# FOTA_MCU_ICSP_Communication.net
KiCad netlist of a schematic drawn in Altium Designer
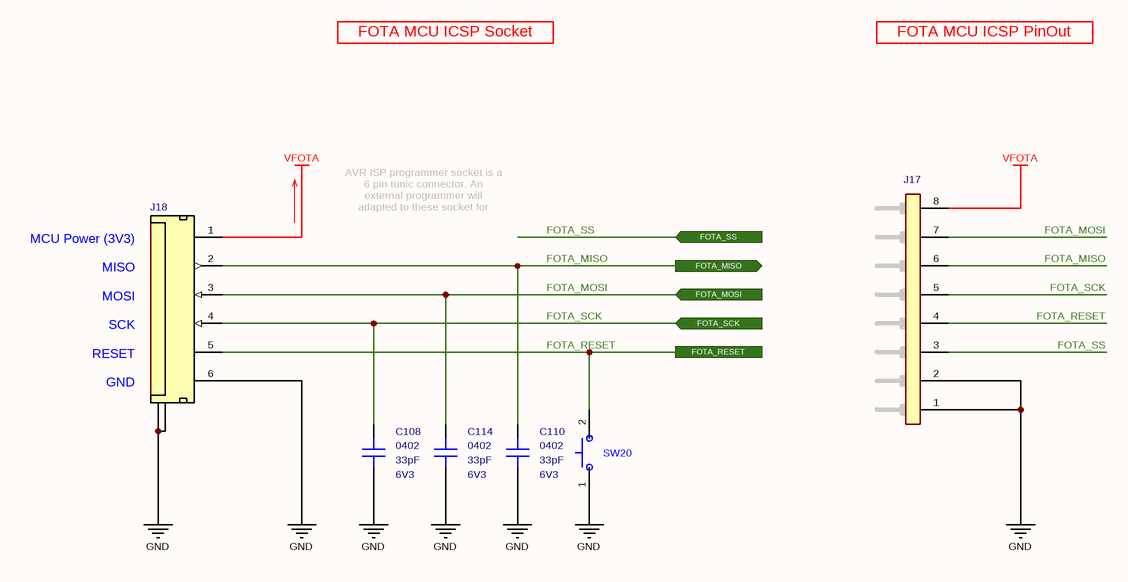
[diagram p0: FOTA MCU ICSP Communication.SchDoc]

(export (version "E")
  (design (tool "Eeschema 10.0.6"))
  (components
    (comp (ref "C108")
      (value "33pF")
      (footprint "CAPACITOR_0402")
      (description "Capacitor - 33pF [0402] (Ceramic)")
      (fields
        (field (name "MANUFACTURER_PART_NUMBER") "C0402C330J9RACAUTO")
        (field (name "MOUSER_PART_NUMBER") "80-C0402C330J9RAUTO")
        (field (name "CASE") "0402")
        (field (name "VOLTAGE") "6V3")
      )
      (libsource (lib "Ovoo_Schematic") (part "Capacitor - 33pF [0402-6V3]"))
    )
    (comp (ref "C110")
      (value "33pF")
      (footprint "CAPACITOR_0402")
      (description "Capacitor - 33pF [0402] (Ceramic)")
      (fields
        (field (name "MANUFACTURER_PART_NUMBER") "C0402C330J9RACAUTO")
        (field (name "MOUSER_PART_NUMBER") "80-C0402C330J9RAUTO")
        (field (name "CASE") "0402")
        (field (name "VOLTAGE") "6V3")
      )
      (libsource (lib "Ovoo_Schematic") (part "Capacitor - 33pF [0402-6V3]"))
    )
    (comp (ref "C114")
      (value "33pF")
      (footprint "CAPACITOR_0402")
      (description "Capacitor - 33pF [0402] (Ceramic)")
      (fields
        (field (name "MANUFACTURER_PART_NUMBER") "C0402C330J9RACAUTO")
        (field (name "MOUSER_PART_NUMBER") "80-C0402C330J9RAUTO")
        (field (name "CASE") "0402")
        (field (name "VOLTAGE") "6V3")
      )
      (libsource (lib "Ovoo_Schematic") (part "Capacitor - 33pF [0402-6V3]"))
    )
    (comp (ref "J17")
      (value "2.54 mm Pitch 8P Male Connector")
      (footprint "8P Header")
      (description "Headers & Wire Housings BREAKAWAY HDR VERT 8")
      (fields
        (field (name "MANUFACTURER PART NUMBER") "22-28-4083")
        (field (name "MOUSER PART NUMBER") "538-22-28-4083")
      )
      (libsource (lib "Ovoo_Library") (part "Connector - Male Header 8P (2.54)"))
    )
    (comp (ref "J18")
      (value "6P Tunic Connector")
      (footprint "Connector_Tunic 6P - H")
      (description "Mini Tunic Connector with 6P")
      (fields (field (name "MANUFACTURER_PART_NUMBER") "53261-0671"))
      (libsource (lib "Ovoo_Schematic") (part "Connector - Mini Tunic 6P (1.25)"))
    )
    (comp (ref "SW20")
      (value "Tactile Switches")
      (footprint "PTS526_Switch")
      (description "Tactile Switches 50mA 12VDC, 5.2x5.2mm, 0.8mm H, 260gf, G leads.")
      (fields
        (field (name "MANUFACTURER PART NUMBER") "PTS526 SK08 SMTR2 LFS")
        (field (name "MOUSER PART NUMBER") "611-PTS526SK08SMTR2L")
      )
      (libsource (lib "Ovoo_Library") (part "Switch - Tactile"))
    )
  )
  (nets
    (net (code "1") (name "/FOTA_MISO") (class "Default")
      (node (ref "C110") (pin "1") (pinfunction "1_1") (pintype "passive"))
      (node (ref "J17") (pin "6") (pinfunction "Pin-6_6") (pintype "passive"))
      (node (ref "J18") (pin "2") (pinfunction "M_DRV_2") (pintype "output"))
    )
    (net (code "2") (name "/FOTA_MOSI") (class "Default")
      (node (ref "C114") (pin "1") (pinfunction "1_1") (pintype "passive"))
      (node (ref "J17") (pin "7") (pinfunction "Pin-7_7") (pintype "passive"))
      (node (ref "J18") (pin "3") (pinfunction "M_DRV_3") (pintype "input"))
    )
    (net (code "3") (name "/FOTA_RESET") (class "Default")
      (node (ref "J17") (pin "4") (pinfunction "Pin-4_4") (pintype "passive"))
      (node (ref "J18") (pin "5") (pinfunction "M_DRV_5") (pintype "passive"))
      (node (ref "SW20") (pin "2") (pinfunction "COM_2") (pintype "passive"))
    )
    (net (code "4") (name "/FOTA_SCK") (class "Default")
      (node (ref "C108") (pin "1") (pinfunction "1_1") (pintype "passive"))
      (node (ref "J17") (pin "5") (pinfunction "Pin-5_5") (pintype "passive"))
      (node (ref "J18") (pin "4") (pinfunction "M_DRV_4") (pintype "input"))
    )
    (net (code "5") (name "/FOTA_SS") (class "Default")
      (node (ref "J17") (pin "3") (pinfunction "Pin-3_3") (pintype "passive"))
    )
    (net (code "6") (name "GND") (class "Default")
      (node (ref "C108") (pin "2") (pinfunction "2_2") (pintype "passive"))
      (node (ref "C110") (pin "2") (pinfunction "2_2") (pintype "passive"))
      (node (ref "C114") (pin "2") (pinfunction "2_2") (pintype "passive"))
      (node (ref "J17") (pin "1") (pinfunction "Pin-1_1") (pintype "passive"))
      (node (ref "J17") (pin "2") (pinfunction "Pin-2_2") (pintype "passive"))
      (node (ref "J18") (pin "6") (pinfunction "M_DRV_6") (pintype "passive"))
      (node (ref "J18") (pin "7") (pinfunction "GND_7") (pintype "passive"))
      (node (ref "J18") (pin "8") (pinfunction "GND_8") (pintype "passive"))
      (node (ref "SW20") (pin "1") (pinfunction "NC_1") (pintype "passive"))
    )
    (net (code "7") (name "VFOTA") (class "Default")
      (node (ref "J17") (pin "8") (pinfunction "Pin-8_8") (pintype "passive"))
      (node (ref "J18") (pin "1") (pinfunction "VBAT_1") (pintype "passive"))
    )
  )
)
